# OsuKB.net
KiCad netlist of a schematic drawn in EAGLE
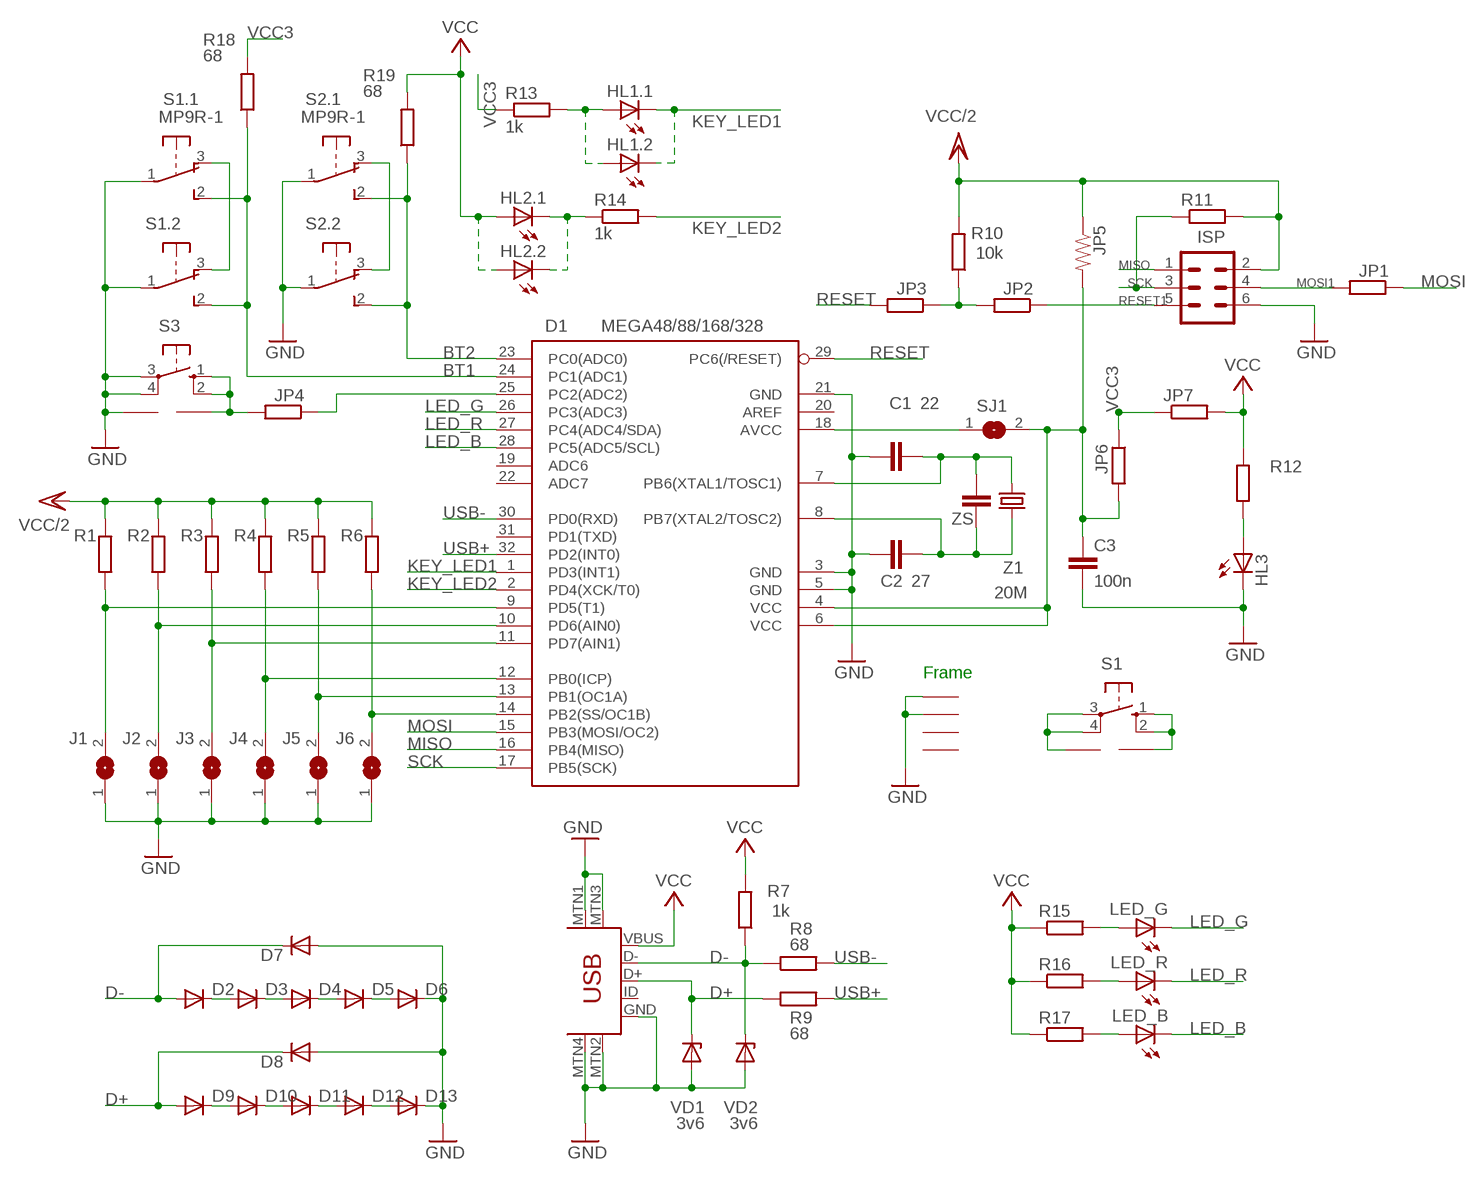
[diagram p0: schematic, sheet 1]

(export (version "E")
  (design (tool "Eeschema 10.0.6"))
  (components
    (comp (ref "C1")
      (value "22")
      (footprint "eagle-import:C0805")
      (libsource (lib "eagle-import") (part "C-EUC0805"))
    )
    (comp (ref "C2")
      (value "27")
      (footprint "eagle-import:C0805")
      (libsource (lib "eagle-import") (part "C-EUC0805"))
    )
    (comp (ref "C3")
      (value "100n")
      (footprint "eagle-import:C0805")
      (libsource (lib "eagle-import") (part "C-EUC0805"))
    )
    (comp (ref "D1")
      (value "MEGA48/88/168/328")
      (footprint "eagle-import:TQFP32-08")
      (fields (field (name "MPN") "ATMEGA8-16AU"))
      (libsource (lib "eagle-import") (part "MEGA8-AI"))
    )
    (comp (ref "D2")
      (value "DIODE-SOD80C")
      (footprint "eagle-import:SOD80C")
      (libsource (lib "eagle-import") (part "DIODE-SOD80C"))
    )
    (comp (ref "D3")
      (value "DIODE-SOD80C")
      (footprint "eagle-import:SOD80C")
      (libsource (lib "eagle-import") (part "DIODE-SOD80C"))
    )
    (comp (ref "D4")
      (value "DIODE-SOD80C")
      (footprint "eagle-import:SOD80C")
      (libsource (lib "eagle-import") (part "DIODE-SOD80C"))
    )
    (comp (ref "D5")
      (value "DIODE-SOD80C")
      (footprint "eagle-import:SOD80C")
      (libsource (lib "eagle-import") (part "DIODE-SOD80C"))
    )
    (comp (ref "D6")
      (value "DIODE-SOD80C")
      (footprint "eagle-import:SOD80C")
      (libsource (lib "eagle-import") (part "DIODE-SOD80C"))
    )
    (comp (ref "D7")
      (value "DIODE-SOD80C")
      (footprint "eagle-import:SOD80C")
      (libsource (lib "eagle-import") (part "DIODE-SOD80C"))
    )
    (comp (ref "D8")
      (value "DIODE-SOD80C")
      (footprint "eagle-import:SOD80C")
      (libsource (lib "eagle-import") (part "DIODE-SOD80C"))
    )
    (comp (ref "D9")
      (value "DIODE-SOD80C")
      (footprint "eagle-import:SOD80C")
      (libsource (lib "eagle-import") (part "DIODE-SOD80C"))
    )
    (comp (ref "D10")
      (value "DIODE-SOD80C")
      (footprint "eagle-import:SOD80C")
      (libsource (lib "eagle-import") (part "DIODE-SOD80C"))
    )
    (comp (ref "D11")
      (value "DIODE-SOD80C")
      (footprint "eagle-import:SOD80C")
      (libsource (lib "eagle-import") (part "DIODE-SOD80C"))
    )
    (comp (ref "D12")
      (value "DIODE-SOD80C")
      (footprint "eagle-import:SOD80C")
      (libsource (lib "eagle-import") (part "DIODE-SOD80C"))
    )
    (comp (ref "D13")
      (value "DIODE-SOD80C")
      (footprint "eagle-import:SOD80C")
      (libsource (lib "eagle-import") (part "DIODE-SOD80C"))
    )
    (comp (ref "GND")
      (value "KB2")
      (footprint "eagle-import:KB2")
      (libsource (lib "eagle-import") (part "KB2"))
    )
    (comp (ref "HL1.1")
      (value "LEDSQR2X5")
      (footprint "eagle-import:LED2X5")
      (libsource (lib "eagle-import") (part "LEDSQR2X5"))
    )
    (comp (ref "HL1.2")
      (value "LEDSQR2X5")
      (footprint "eagle-import:LED2X5")
      (libsource (lib "eagle-import") (part "LEDSQR2X5"))
    )
    (comp (ref "HL2.1")
      (value "LEDSQR2X5")
      (footprint "eagle-import:LED2X5")
      (libsource (lib "eagle-import") (part "LEDSQR2X5"))
    )
    (comp (ref "HL2.2")
      (value "LEDSQR2X5")
      (footprint "eagle-import:LED2X5")
      (libsource (lib "eagle-import") (part "LEDSQR2X5"))
    )
    (comp (ref "HL3")
      (value "LEDSML0805")
      (footprint "eagle-import:SML0805")
      (libsource (lib "eagle-import") (part "LEDSML0805"))
    )
    (comp (ref "ISP")
      (value "MA03-2")
      (footprint "eagle-import:MA03-2")
      (libsource (lib "eagle-import") (part "MA03-2"))
    )
    (comp (ref "J1") (value "SJ") (footprint "eagle-import:SJ") (libsource (lib "eagle-import") (part "SJ")))
    (comp (ref "J2") (value "SJ") (footprint "eagle-import:SJ") (libsource (lib "eagle-import") (part "SJ")))
    (comp (ref "J3") (value "SJ") (footprint "eagle-import:SJ") (libsource (lib "eagle-import") (part "SJ")))
    (comp (ref "J4") (value "SJ") (footprint "eagle-import:SJ") (libsource (lib "eagle-import") (part "SJ")))
    (comp (ref "J5") (value "SJ") (footprint "eagle-import:SJ") (libsource (lib "eagle-import") (part "SJ")))
    (comp (ref "J6") (value "SJ") (footprint "eagle-import:SJ") (libsource (lib "eagle-import") (part "SJ")))
    (comp (ref "JP1")
      (value "R-EU_R1206W")
      (footprint "eagle-import:R1206W")
      (libsource (lib "eagle-import") (part "rcl_R-EU_R1206W"))
    )
    (comp (ref "JP2")
      (value "R-EU_R1206W")
      (footprint "eagle-import:R1206W")
      (libsource (lib "eagle-import") (part "rcl_R-EU_R1206W"))
    )
    (comp (ref "JP3")
      (value "R-EU_R1206W")
      (footprint "eagle-import:R1206W")
      (libsource (lib "eagle-import") (part "rcl_R-EU_R1206W"))
    )
    (comp (ref "JP4")
      (value "R-EU_R1206W")
      (footprint "eagle-import:R1206W")
      (libsource (lib "eagle-import") (part "rcl_R-EU_R1206W"))
    )
    (comp (ref "JP5")
      (value "RESISTOR0805-RES")
      (footprint "eagle-import:0805")
      (libsource (lib "eagle-import") (part "RESISTOR0805-RES"))
    )
    (comp (ref "JP6")
      (value "R-EU_R1206W")
      (footprint "eagle-import:R1206W")
      (libsource (lib "eagle-import") (part "rcl_R-EU_R1206W"))
    )
    (comp (ref "JP7")
      (value "R-EU_R1206W")
      (footprint "eagle-import:R1206W")
      (libsource (lib "eagle-import") (part "R-EU_R1206W"))
    )
    (comp (ref "LED_B")
      (value "LEDKA-3528ASYC")
      (footprint "eagle-import:KA-3528ASYC")
      (libsource (lib "eagle-import") (part "LEDKA-3528ASYC"))
    )
    (comp (ref "LED_G")
      (value "LEDKA-3528ASYC")
      (footprint "eagle-import:KA-3528ASYC")
      (libsource (lib "eagle-import") (part "LEDKA-3528ASYC"))
    )
    (comp (ref "LED_R")
      (value "LEDKA-3528ASYC")
      (footprint "eagle-import:KA-3528ASYC")
      (libsource (lib "eagle-import") (part "LEDKA-3528ASYC"))
    )
    (comp (ref "R1")
      (value "R-EU_R1206W")
      (footprint "eagle-import:R1206W")
      (libsource (lib "eagle-import") (part "rcl_R-EU_R1206W"))
    )
    (comp (ref "R2")
      (value "R-EU_R1206W")
      (footprint "eagle-import:R1206W")
      (libsource (lib "eagle-import") (part "rcl_R-EU_R1206W"))
    )
    (comp (ref "R3")
      (value "R-EU_R1206W")
      (footprint "eagle-import:R1206W")
      (libsource (lib "eagle-import") (part "rcl_R-EU_R1206W"))
    )
    (comp (ref "R4")
      (value "R-EU_R1206W")
      (footprint "eagle-import:R1206W")
      (libsource (lib "eagle-import") (part "rcl_R-EU_R1206W"))
    )
    (comp (ref "R5")
      (value "R-EU_R1206W")
      (footprint "eagle-import:R1206W")
      (libsource (lib "eagle-import") (part "rcl_R-EU_R1206W"))
    )
    (comp (ref "R6")
      (value "R-EU_R0805")
      (footprint "eagle-import:R0805")
      (libsource (lib "eagle-import") (part "rcl_R-EU_R0805"))
    )
    (comp (ref "R7")
      (value "1k")
      (footprint "eagle-import:R0805")
      (libsource (lib "eagle-import") (part "rcl_R-EU_R0805"))
    )
    (comp (ref "R8")
      (value "68")
      (footprint "eagle-import:R0805")
      (libsource (lib "eagle-import") (part "rcl_R-EU_R0805"))
    )
    (comp (ref "R9")
      (value "68")
      (footprint "eagle-import:R0805")
      (libsource (lib "eagle-import") (part "rcl_R-EU_R0805"))
    )
    (comp (ref "R10")
      (value "10k")
      (footprint "eagle-import:R1206W")
      (libsource (lib "eagle-import") (part "rcl_R-EU_R1206W"))
    )
    (comp (ref "R11")
      (value "R-EU_R0402")
      (footprint "eagle-import:R0402")
      (libsource (lib "eagle-import") (part "rcl_R-EU_R0402"))
    )
    (comp (ref "R12")
      (value "R-EU_R0805")
      (footprint "eagle-import:R0805")
      (libsource (lib "eagle-import") (part "rcl_R-EU_R0805"))
    )
    (comp (ref "R13")
      (value "1k")
      (footprint "eagle-import:R1206W")
      (libsource (lib "eagle-import") (part "R-EU_R1206W"))
    )
    (comp (ref "R14")
      (value "1k")
      (footprint "eagle-import:0207_12")
      (libsource (lib "eagle-import") (part "rcl_R-EU_0207/12"))
    )
    (comp (ref "R15")
      (value "R-EU_R0805")
      (footprint "eagle-import:R0805")
      (libsource (lib "eagle-import") (part "rcl_R-EU_R0805"))
    )
    (comp (ref "R16")
      (value "R-EU_R0805")
      (footprint "eagle-import:R0805")
      (libsource (lib "eagle-import") (part "rcl_R-EU_R0805"))
    )
    (comp (ref "R17")
      (value "R-EU_R0805")
      (footprint "eagle-import:R0805")
      (libsource (lib "eagle-import") (part "rcl_R-EU_R0805"))
    )
    (comp (ref "R18")
      (value "68")
      (footprint "eagle-import:R0805")
      (libsource (lib "eagle-import") (part "rcl_R-EU_R0805"))
    )
    (comp (ref "R19")
      (value "68")
      (footprint "eagle-import:R0805")
      (libsource (lib "eagle-import") (part "rcl_R-EU_R0805"))
    )
    (comp (ref "S1")
      (value "10-XX")
      (footprint "eagle-import:B3F-10XX")
      (fields
        (field (name "MPN") "B3F-1000")
        (field (name "MPN_1") "B3F-1000")
        (field (name "OC_FARNELL") "176432")
        (field (name "OC_NEWARK") "36M3542")
      )
      (libsource (lib "eagle-import") (part "10-XX"))
    )
    (comp (ref "S1.1")
      (value "MP9R-1")
      (footprint "eagle-import:MP5")
      (libsource (lib "eagle-import") (part "MP5"))
    )
    (comp (ref "S1.2")
      (value "MP5")
      (footprint "eagle-import:MP5")
      (libsource (lib "eagle-import") (part "MP5"))
    )
    (comp (ref "S2.1")
      (value "MP9R-1")
      (footprint "eagle-import:MP5")
      (libsource (lib "eagle-import") (part "MP5"))
    )
    (comp (ref "S2.2")
      (value "MP5")
      (footprint "eagle-import:MP5")
      (libsource (lib "eagle-import") (part "MP5"))
    )
    (comp (ref "S3")
      (value "10-XX")
      (footprint "eagle-import:B3F-10XX")
      (fields (field (name "MPN") "B3F-1000"))
      (libsource (lib "eagle-import") (part "10-XX"))
    )
    (comp (ref "SJ1") (value "SJ") (footprint "eagle-import:SJ") (libsource (lib "eagle-import") (part "SJ")))
    (comp (ref "U$1")
      (value "PROGRAMMER_5.08")
      (footprint "eagle-import:PROGRAMMER_KEY")
      (libsource (lib "eagle-import") (part "PROGRAMMER_5.08"))
    )
    (comp (ref "U$6")
      (value "PROGRAMMER_5.08")
      (footprint "eagle-import:PROGRAMMER_KEY")
      (libsource (lib "eagle-import") (part "PROGRAMMER_5.08"))
    )
    (comp (ref "VD1")
      (value "3v6")
      (footprint "eagle-import:DO34Z7")
      (libsource (lib "eagle-import") (part "ZENER-DIODEDO34-7"))
    )
    (comp (ref "VD2")
      (value "3v6")
      (footprint "eagle-import:DO34Z7")
      (libsource (lib "eagle-import") (part "ZENER-DIODEDO34-7"))
    )
    (comp (ref "X1")
      (value "USB-MINIB-5PIN")
      (footprint "eagle-import:USB-MINIB")
      (libsource (lib "eagle-import") (part "USB-MINIB-5PIN"))
    )
    (comp (ref "Z1")
      (value "20M")
      (footprint "eagle-import:HC49_S")
      (libsource (lib "eagle-import") (part "CRYSTALHC49S"))
    )
    (comp (ref "ZS")
      (value "C-EUC1812K")
      (footprint "eagle-import:C1812K")
      (libsource (lib "eagle-import") (part "C-EUC1812K"))
    )
  )
  (nets
    (net (code "1") (name "/BT1") (class "Default")
      (node (ref "D1") (pin "24") (pinfunction "PC1(ADC1)_24") (pintype "bidirectional"))
      (node (ref "R18") (pin "1") (pinfunction "1_1") (pintype "passive"))
      (node (ref "S1.1") (pin "2") (pinfunction "2_2") (pintype "passive"))
      (node (ref "S1.2") (pin "2") (pinfunction "2_2") (pintype "passive"))
    )
    (net (code "2") (name "/BT2") (class "Default")
      (node (ref "D1") (pin "23") (pinfunction "PC0(ADC0)_23") (pintype "bidirectional"))
      (node (ref "R19") (pin "1") (pinfunction "1_1") (pintype "passive"))
      (node (ref "S2.1") (pin "2") (pinfunction "2_2") (pintype "passive"))
      (node (ref "S2.2") (pin "2") (pinfunction "2_2") (pintype "passive"))
    )
    (net (code "3") (name "/D+") (class "Default")
      (node (ref "D8") (pin "C") (pinfunction "C_C") (pintype "passive"))
      (node (ref "D9") (pin "A") (pinfunction "A_A") (pintype "passive"))
      (node (ref "R9") (pin "1") (pinfunction "1_1") (pintype "passive"))
      (node (ref "VD1") (pin "C") (pinfunction "C_C") (pintype "passive"))
      (node (ref "X1") (pin "D+") (pinfunction "D+_D+") (pintype "bidirectional"))
    )
    (net (code "4") (name "/D-") (class "Default")
      (node (ref "D2") (pin "A") (pinfunction "A_A") (pintype "passive"))
      (node (ref "D7") (pin "C") (pinfunction "C_C") (pintype "passive"))
      (node (ref "R7") (pin "1") (pinfunction "1_1") (pintype "passive"))
      (node (ref "R8") (pin "1") (pinfunction "1_1") (pintype "passive"))
      (node (ref "VD2") (pin "C") (pinfunction "C_C") (pintype "passive"))
      (node (ref "X1") (pin "D-") (pinfunction "D-_D-") (pintype "bidirectional"))
    )
    (net (code "5") (name "/KEY_LED1") (class "Default")
      (node (ref "D1") (pin "1") (pinfunction "PD3(INT1)_1") (pintype "bidirectional"))
      (node (ref "HL1.1") (pin "K") (pinfunction "C_K") (pintype "passive"))
      (node (ref "HL1.2") (pin "K") (pinfunction "C_K") (pintype "passive"))
    )
    (net (code "6") (name "/KEY_LED2") (class "Default")
      (node (ref "D1") (pin "2") (pinfunction "PD4(XCK/T0)_2") (pintype "bidirectional"))
      (node (ref "R14") (pin "2") (pinfunction "2_2") (pintype "passive"))
    )
    (net (code "7") (name "/LED_B") (class "Default")
      (node (ref "D1") (pin "28") (pinfunction "PC5(ADC5/SCL)_28") (pintype "bidirectional"))
      (node (ref "LED_B") (pin "C") (pinfunction "C_C") (pintype "passive"))
    )
    (net (code "8") (name "/LED_G") (class "Default")
      (node (ref "D1") (pin "26") (pinfunction "PC3(ADC3)_26") (pintype "bidirectional"))
      (node (ref "LED_G") (pin "C") (pinfunction "C_C") (pintype "passive"))
    )
    (net (code "9") (name "/LED_R") (class "Default")
      (node (ref "D1") (pin "27") (pinfunction "PC4(ADC4/SDA)_27") (pintype "bidirectional"))
      (node (ref "LED_R") (pin "C") (pinfunction "C_C") (pintype "passive"))
    )
    (net (code "10") (name "/MISO") (class "Default")
      (node (ref "D1") (pin "16") (pinfunction "PB4(MISO)_16") (pintype "bidirectional"))
      (node (ref "ISP") (pin "1") (pinfunction "1_1") (pintype "passive"))
    )
    (net (code "11") (name "/MOSI") (class "Default")
      (node (ref "D1") (pin "15") (pinfunction "PB3(MOSI/OC2)_15") (pintype "bidirectional"))
      (node (ref "JP1") (pin "1") (pinfunction "1_1") (pintype "passive"))
    )
    (net (code "12") (name "/MOSI1") (class "Default")
      (node (ref "ISP") (pin "4") (pinfunction "4_4") (pintype "passive"))
      (node (ref "JP1") (pin "2") (pinfunction "2_2") (pintype "passive"))
    )
    (net (code "13") (name "/RESET") (class "Default")
      (node (ref "D1") (pin "29") (pinfunction "PC6(/RESET)_29") (pintype "bidirectional"))
      (node (ref "JP3") (pin "2") (pinfunction "2_2") (pintype "passive"))
    )
    (net (code "14") (name "/RESET1") (class "Default")
      (node (ref "ISP") (pin "5") (pinfunction "5_5") (pintype "passive"))
      (node (ref "JP2") (pin "1") (pinfunction "1_1") (pintype "passive"))
    )
    (net (code "15") (name "/SCK") (class "Default")
      (node (ref "D1") (pin "17") (pinfunction "PB5(SCK)_17") (pintype "bidirectional"))
      (node (ref "ISP") (pin "3") (pinfunction "3_3") (pintype "passive"))
      (node (ref "R11") (pin "1") (pinfunction "1_1") (pintype "passive"))
    )
    (net (code "16") (name "/USB+") (class "Default")
      (node (ref "D1") (pin "32") (pinfunction "PD2(INT0)_32") (pintype "bidirectional"))
      (node (ref "R9") (pin "2") (pinfunction "2_2") (pintype "passive"))
    )
    (net (code "17") (name "/USB-") (class "Default")
      (node (ref "D1") (pin "30") (pinfunction "PD0(RXD)_30") (pintype "bidirectional"))
      (node (ref "R8") (pin "2") (pinfunction "2_2") (pintype "passive"))
    )
    (net (code "18") (name "/VCC3") (class "Default")
      (node (ref "JP6") (pin "1") (pinfunction "1_1") (pintype "passive"))
      (node (ref "JP7") (pin "1") (pinfunction "1_1") (pintype "passive"))
      (node (ref "R13") (pin "1") (pinfunction "1_1") (pintype "passive"))
      (node (ref "R18") (pin "2") (pinfunction "2_2") (pintype "passive"))
    )
    (net (code "19") (name "GND") (class "Default")
      (node (ref "C1") (pin "1") (pinfunction "1_1") (pintype "passive"))
      (node (ref "C2") (pin "1") (pinfunction "1_1") (pintype "passive"))
      (node (ref "C3") (pin "2") (pinfunction "2_2") (pintype "passive"))
      (node (ref "D1") (pin "21") (pinfunction "GND_21") (pintype "power_in"))
      (node (ref "D1") (pin "3") (pinfunction "GND_3") (pintype "power_in"))
      (node (ref "D1") (pin "5") (pinfunction "GND_5") (pintype "power_in"))
      (node (ref "D13") (pin "C") (pinfunction "C_C") (pintype "passive"))
      (node (ref "D6") (pin "C") (pinfunction "C_C") (pintype "passive"))
      (node (ref "D7") (pin "A") (pinfunction "A_A") (pintype "passive"))
      (node (ref "D8") (pin "A") (pinfunction "A_A") (pintype "passive"))
      (node (ref "GND") (pin "P$1") (pinfunction "1_P$1") (pintype "bidirectional"))
      (node (ref "GND") (pin "P$2") (pinfunction "2_P$2") (pintype "bidirectional"))
      (node (ref "HL3") (pin "C") (pinfunction "C_C") (pintype "passive"))
      (node (ref "ISP") (pin "6") (pinfunction "6_6") (pintype "passive"))
      (node (ref "J1") (pin "1") (pinfunction "1_1") (pintype "passive"))
      (node (ref "J2") (pin "1") (pinfunction "1_1") (pintype "passive"))
      (node (ref "J3") (pin "1") (pinfunction "1_1") (pintype "passive"))
      (node (ref "J4") (pin "1") (pinfunction "1_1") (pintype "passive"))
      (node (ref "J5") (pin "1") (pinfunction "1_1") (pintype "passive"))
      (node (ref "J6") (pin "1") (pinfunction "1_1") (pintype "passive"))
      (node (ref "S1.1") (pin "1") (pinfunction "1_1") (pintype "passive"))
      (node (ref "S1.2") (pin "1") (pinfunction "1_1") (pintype "passive"))
      (node (ref "S2.1") (pin "1") (pinfunction "1_1") (pintype "passive"))
      (node (ref "S2.2") (pin "1") (pinfunction "1_1") (pintype "passive"))
      (node (ref "S3") (pin "3") (pinfunction "P_3") (pintype "passive"))
      (node (ref "S3") (pin "4") (pinfunction "P1_4") (pintype "passive"))
      (node (ref "U$6") (pin "P$1") (pinfunction "P$1_P$1") (pintype "bidirectional"))
      (node (ref "VD1") (pin "A") (pinfunction "A_A") (pintype "passive"))
      (node (ref "VD2") (pin "A") (pinfunction "A_A") (pintype "passive"))
      (node (ref "X1") (pin "GND") (pinfunction "GND_GND") (pintype "bidirectional"))
      (node (ref "X1") (pin "MTN1") (pinfunction "MTN2_MTN1") (pintype "bidirectional"))
      (node (ref "X1") (pin "MTN2") (pinfunction "MTN3_MTN2") (pintype "bidirectional"))
      (node (ref "X1") (pin "MTN3") (pinfunction "MTN1_MTN3") (pintype "bidirectional"))
      (node (ref "X1") (pin "MTN4") (pinfunction "MTN4_MTN4") (pintype "bidirectional"))
    )
    (net (code "20") (name "Net-(C3-Pad1)") (class "Default")
      (node (ref "C3") (pin "1") (pinfunction "1_1") (pintype "passive"))
      (node (ref "D1") (pin "4") (pinfunction "VCC_4") (pintype "power_in"))
      (node (ref "D1") (pin "6") (pinfunction "VCC_6") (pintype "power_in"))
      (node (ref "JP5") (pin "2") (pinfunction "2_2") (pintype "passive"))
      (node (ref "JP6") (pin "2") (pinfunction "2_2") (pintype "passive"))
      (node (ref "SJ1") (pin "2") (pinfunction "2_2") (pintype "passive"))
    )
    (net (code "21") (name "Net-(D1-AVCC)") (class "Default")
      (node (ref "D1") (pin "18") (pinfunction "AVCC_18") (pintype "power_in"))
      (node (ref "SJ1") (pin "1") (pinfunction "1_1") (pintype "passive"))
    )
    (net (code "22") (name "Net-(D1-PB0(ICP))") (class "Default")
      (node (ref "D1") (pin "12") (pinfunction "PB0(ICP)_12") (pintype "bidirectional"))
      (node (ref "J4") (pin "2") (pinfunction "2_2") (pintype "passive"))
      (node (ref "R4") (pin "1") (pinfunction "1_1") (pintype "passive"))
    )
    (net (code "23") (name "Net-(D1-PB1(OC1A))") (class "Default")
      (node (ref "D1") (pin "13") (pinfunction "PB1(OC1A)_13") (pintype "bidirectional"))
      (node (ref "J5") (pin "2") (pinfunction "2_2") (pintype "passive"))
      (node (ref "R5") (pin "1") (pinfunction "1_1") (pintype "passive"))
    )
    (net (code "24") (name "Net-(D1-PB2(SS{slash}OC1B))") (class "Default")
      (node (ref "D1") (pin "14") (pinfunction "PB2(SS/OC1B)_14") (pintype "bidirectional"))
      (node (ref "J6") (pin "2") (pinfunction "2_2") (pintype "passive"))
      (node (ref "R6") (pin "1") (pinfunction "1_1") (pintype "passive"))
    )
    (net (code "25") (name "Net-(D1-PB6(XTAL1{slash}TOSC1))") (class "Default")
      (node (ref "C1") (pin "2") (pinfunction "2_2") (pintype "passive"))
      (node (ref "D1") (pin "7") (pinfunction "PB6(XTAL1/TOSC1)_7") (pintype "bidirectional"))
      (node (ref "Z1") (pin "1") (pinfunction "1_1") (pintype "passive"))
      (node (ref "ZS") (pin "1") (pinfunction "1_1") (pintype "passive"))
    )
    (net (code "26") (name "Net-(D1-PB7(XTAL2{slash}TOSC2))") (class "Default")
      (node (ref "C2") (pin "2") (pinfunction "2_2") (pintype "passive"))
      (node (ref "D1") (pin "8") (pinfunction "PB7(XTAL2/TOSC2)_8") (pintype "bidirectional"))
      (node (ref "Z1") (pin "2") (pinfunction "2_2") (pintype "passive"))
      (node (ref "ZS") (pin "2") (pinfunction "2_2") (pintype "passive"))
    )
    (net (code "27") (name "Net-(D1-PC2(ADC2))") (class "Default")
      (node (ref "D1") (pin "25") (pinfunction "PC2(ADC2)_25") (pintype "bidirectional"))
      (node (ref "JP4") (pin "1") (pinfunction "1_1") (pintype "passive"))
    )
    (net (code "28") (name "Net-(D1-PD5(T1))") (class "Default")
      (node (ref "D1") (pin "9") (pinfunction "PD5(T1)_9") (pintype "bidirectional"))
      (node (ref "J1") (pin "2") (pinfunction "2_2") (pintype "passive"))
      (node (ref "R1") (pin "1") (pinfunction "1_1") (pintype "passive"))
    )
    (net (code "29") (name "Net-(D1-PD6(AIN0))") (class "Default")
      (node (ref "D1") (pin "10") (pinfunction "PD6(AIN0)_10") (pintype "bidirectional"))
      (node (ref "J2") (pin "2") (pinfunction "2_2") (pintype "passive"))
      (node (ref "R2") (pin "1") (pinfunction "1_1") (pintype "passive"))
    )
    (net (code "30") (name "Net-(D1-PD7(AIN1))") (class "Default")
      (node (ref "D1") (pin "11") (pinfunction "PD7(AIN1)_11") (pintype "bidirectional"))
      (node (ref "J3") (pin "2") (pinfunction "2_2") (pintype "passive"))
      (node (ref "R3") (pin "1") (pinfunction "1_1") (pintype "passive"))
    )
    (net (code "31") (name "Net-(D2-PadC)") (class "Default")
      (node (ref "D2") (pin "C") (pinfunction "C_C") (pintype "passive"))
      (node (ref "D3") (pin "A") (pinfunction "A_A") (pintype "passive"))
    )
    (net (code "32") (name "Net-(D3-PadC)") (class "Default")
      (node (ref "D3") (pin "C") (pinfunction "C_C") (pintype "passive"))
      (node (ref "D4") (pin "A") (pinfunction "A_A") (pintype "passive"))
    )
    (net (code "33") (name "Net-(D4-PadC)") (class "Default")
      (node (ref "D4") (pin "C") (pinfunction "C_C") (pintype "passive"))
      (node (ref "D5") (pin "A") (pinfunction "A_A") (pintype "passive"))
    )
    (net (code "34") (name "Net-(D5-PadC)") (class "Default")
      (node (ref "D5") (pin "C") (pinfunction "C_C") (pintype "passive"))
      (node (ref "D6") (pin "A") (pinfunction "A_A") (pintype "passive"))
    )
    (net (code "35") (name "Net-(D10-PadA)") (class "Default")
      (node (ref "D10") (pin "A") (pinfunction "A_A") (pintype "passive"))
      (node (ref "D9") (pin "C") (pinfunction "C_C") (pintype "passive"))
    )
    (net (code "36") (name "Net-(D10-PadC)") (class "Default")
      (node (ref "D10") (pin "C") (pinfunction "C_C") (pintype "passive"))
      (node (ref "D11") (pin "A") (pinfunction "A_A") (pintype "passive"))
    )
    (net (code "37") (name "Net-(D11-PadC)") (class "Default")
      (node (ref "D11") (pin "C") (pinfunction "C_C") (pintype "passive"))
      (node (ref "D12") (pin "A") (pinfunction "A_A") (pintype "passive"))
    )
    (net (code "38") (name "Net-(D12-PadC)") (class "Default")
      (node (ref "D12") (pin "C") (pinfunction "C_C") (pintype "passive"))
      (node (ref "D13") (pin "A") (pinfunction "A_A") (pintype "passive"))
    )
    (net (code "39") (name "Net-(HL1.1-PadA)") (class "Default")
      (node (ref "HL1.1") (pin "A") (pinfunction "A_A") (pintype "passive"))
      (node (ref "HL1.2") (pin "A") (pinfunction "A_A") (pintype "passive"))
      (node (ref "R13") (pin "2") (pinfunction "2_2") (pintype "passive"))
    )
    (net (code "40") (name "Net-(HL2.1-C)") (class "Default")
      (node (ref "HL2.1") (pin "K") (pinfunction "C_K") (pintype "passive"))
      (node (ref "HL2.2") (pin "K") (pinfunction "C_K") (pintype "passive"))
      (node (ref "R14") (pin "1") (pinfunction "1_1") (pintype "passive"))
    )
    (net (code "41") (name "Net-(HL3-PadA)") (class "Default")
      (node (ref "HL3") (pin "A") (pinfunction "A_A") (pintype "passive"))
      (node (ref "R12") (pin "1") (pinfunction "1_1") (pintype "passive"))
    )
    (net (code "42") (name "Net-(JP2-Pad2)") (class "Default")
      (node (ref "JP2") (pin "2") (pinfunction "2_2") (pintype "passive"))
      (node (ref "JP3") (pin "1") (pinfunction "1_1") (pintype "passive"))
      (node (ref "R10") (pin "1") (pinfunction "1_1") (pintype "passive"))
    )
    (net (code "43") (name "Net-(LED_B-PadA)") (class "Default")
      (node (ref "LED_B") (pin "A") (pinfunction "A_A") (pintype "passive"))
      (node (ref "R17") (pin "2") (pinfunction "2_2") (pintype "passive"))
    )
    (net (code "44") (name "Net-(LED_G-PadA)") (class "Default")
      (node (ref "LED_G") (pin "A") (pinfunction "A_A") (pintype "passive"))
      (node (ref "R15") (pin "2") (pinfunction "2_2") (pintype "passive"))
    )
    (net (code "45") (name "Net-(LED_R-PadA)") (class "Default")
      (node (ref "LED_R") (pin "A") (pinfunction "A_A") (pintype "passive"))
      (node (ref "R16") (pin "2") (pinfunction "2_2") (pintype "passive"))
    )
    (net (code "46") (name "Net-(S1-P)") (class "Default")
      (node (ref "S1") (pin "3") (pinfunction "P_3") (pintype "passive"))
      (node (ref "S1") (pin "4") (pinfunction "P1_4") (pintype "passive"))
      (node (ref "U$1") (pin "P$1") (pinfunction "P$1_P$1") (pintype "bidirectional"))
    )
    (net (code "47") (name "Net-(S1-S)") (class "Default")
      (node (ref "S1") (pin "1") (pinfunction "S_1") (pintype "passive"))
      (node (ref "S1") (pin "2") (pinfunction "S1_2") (pintype "passive"))
      (node (ref "U$1") (pin "P$2") (pinfunction "P$2_P$2") (pintype "bidirectional"))
    )
    (net (code "48") (name "Net-(S1.1-Pad3)") (class "Default")
      (node (ref "S1.1") (pin "3") (pinfunction "3_3") (pintype "passive"))
      (node (ref "S1.2") (pin "3") (pinfunction "3_3") (pintype "passive"))
    )
    (net (code "49") (name "Net-(S2.1-Pad3)") (class "Default")
      (node (ref "S2.1") (pin "3") (pinfunction "3_3") (pintype "passive"))
      (node (ref "S2.2") (pin "3") (pinfunction "3_3") (pintype "passive"))
    )
    (net (code "50") (name "Net-(S3-S)") (class "Default")
      (node (ref "JP4") (pin "2") (pinfunction "2_2") (pintype "passive"))
      (node (ref "S3") (pin "1") (pinfunction "S_1") (pintype "passive"))
      (node (ref "S3") (pin "2") (pinfunction "S1_2") (pintype "passive"))
      (node (ref "U$6") (pin "P$2") (pinfunction "P$2_P$2") (pintype "bidirectional"))
    )
    (net (code "51") (name "VCC") (class "Default")
      (node (ref "HL2.1") (pin "A") (pinfunction "A_A") (pintype "passive"))
      (node (ref "HL2.2") (pin "A") (pinfunction "A_A") (pintype "passive"))
      (node (ref "JP7") (pin "2") (pinfunction "2_2") (pintype "passive"))
      (node (ref "R12") (pin "2") (pinfunction "2_2") (pintype "passive"))
      (node (ref "R15") (pin "1") (pinfunction "1_1") (pintype "passive"))
      (node (ref "R16") (pin "1") (pinfunction "1_1") (pintype "passive"))
      (node (ref "R17") (pin "1") (pinfunction "1_1") (pintype "passive"))
      (node (ref "R19") (pin "2") (pinfunction "2_2") (pintype "passive"))
      (node (ref "R7") (pin "2") (pinfunction "2_2") (pintype "passive"))
      (node (ref "X1") (pin "VBUS") (pinfunction "VBUS_VBUS") (pintype "bidirectional"))
    )
    (net (code "52") (name "VCC{slash}2") (class "Default")
      (node (ref "ISP") (pin "2") (pinfunction "2_2") (pintype "passive"))
      (node (ref "JP5") (pin "1") (pinfunction "1_1") (pintype "passive"))
      (node (ref "R1") (pin "2") (pinfunction "2_2") (pintype "passive"))
      (node (ref "R10") (pin "2") (pinfunction "2_2") (pintype "passive"))
      (node (ref "R11") (pin "2") (pinfunction "2_2") (pintype "passive"))
      (node (ref "R2") (pin "2") (pinfunction "2_2") (pintype "passive"))
      (node (ref "R3") (pin "2") (pinfunction "2_2") (pintype "passive"))
      (node (ref "R4") (pin "2") (pinfunction "2_2") (pintype "passive"))
      (node (ref "R5") (pin "2") (pinfunction "2_2") (pintype "passive"))
      (node (ref "R6") (pin "2") (pinfunction "2_2") (pintype "passive"))
    )
    (net (code "53") (name "unconnected-(D1-ADC6-Pad19)") (class "Default")
      (node (ref "D1") (pin "19") (pinfunction "ADC6_19") (pintype "bidirectional"))
    )
    (net (code "54") (name "unconnected-(D1-ADC7-Pad22)") (class "Default")
      (node (ref "D1") (pin "22") (pinfunction "ADC7_22") (pintype "bidirectional"))
    )
    (net (code "55") (name "unconnected-(D1-AREF-Pad20)") (class "Default")
      (node (ref "D1") (pin "20") (pinfunction "AREF_20") (pintype "passive"))
    )
    (net (code "56") (name "unconnected-(D1-PD1(TXD)-Pad31)") (class "Default")
      (node (ref "D1") (pin "31") (pinfunction "PD1(TXD)_31") (pintype "bidirectional"))
    )
    (net (code "57") (name "unconnected-(GND-3-PadP$3)") (class "Default")
      (node (ref "GND") (pin "P$3") (pinfunction "3_P$3") (pintype "bidirectional"))
    )
    (net (code "58") (name "unconnected-(GND-4-PadP$4)") (class "Default")
      (node (ref "GND") (pin "P$4") (pinfunction "4_P$4") (pintype "bidirectional"))
    )
    (net (code "59") (name "unconnected-(X1-PadID)") (class "Default")
      (node (ref "X1") (pin "ID") (pinfunction "ID_ID") (pintype "bidirectional"))
    )
  )
)
